# FPGA_Bank_1.net
KiCad netlist of a schematic drawn in Altium Designer
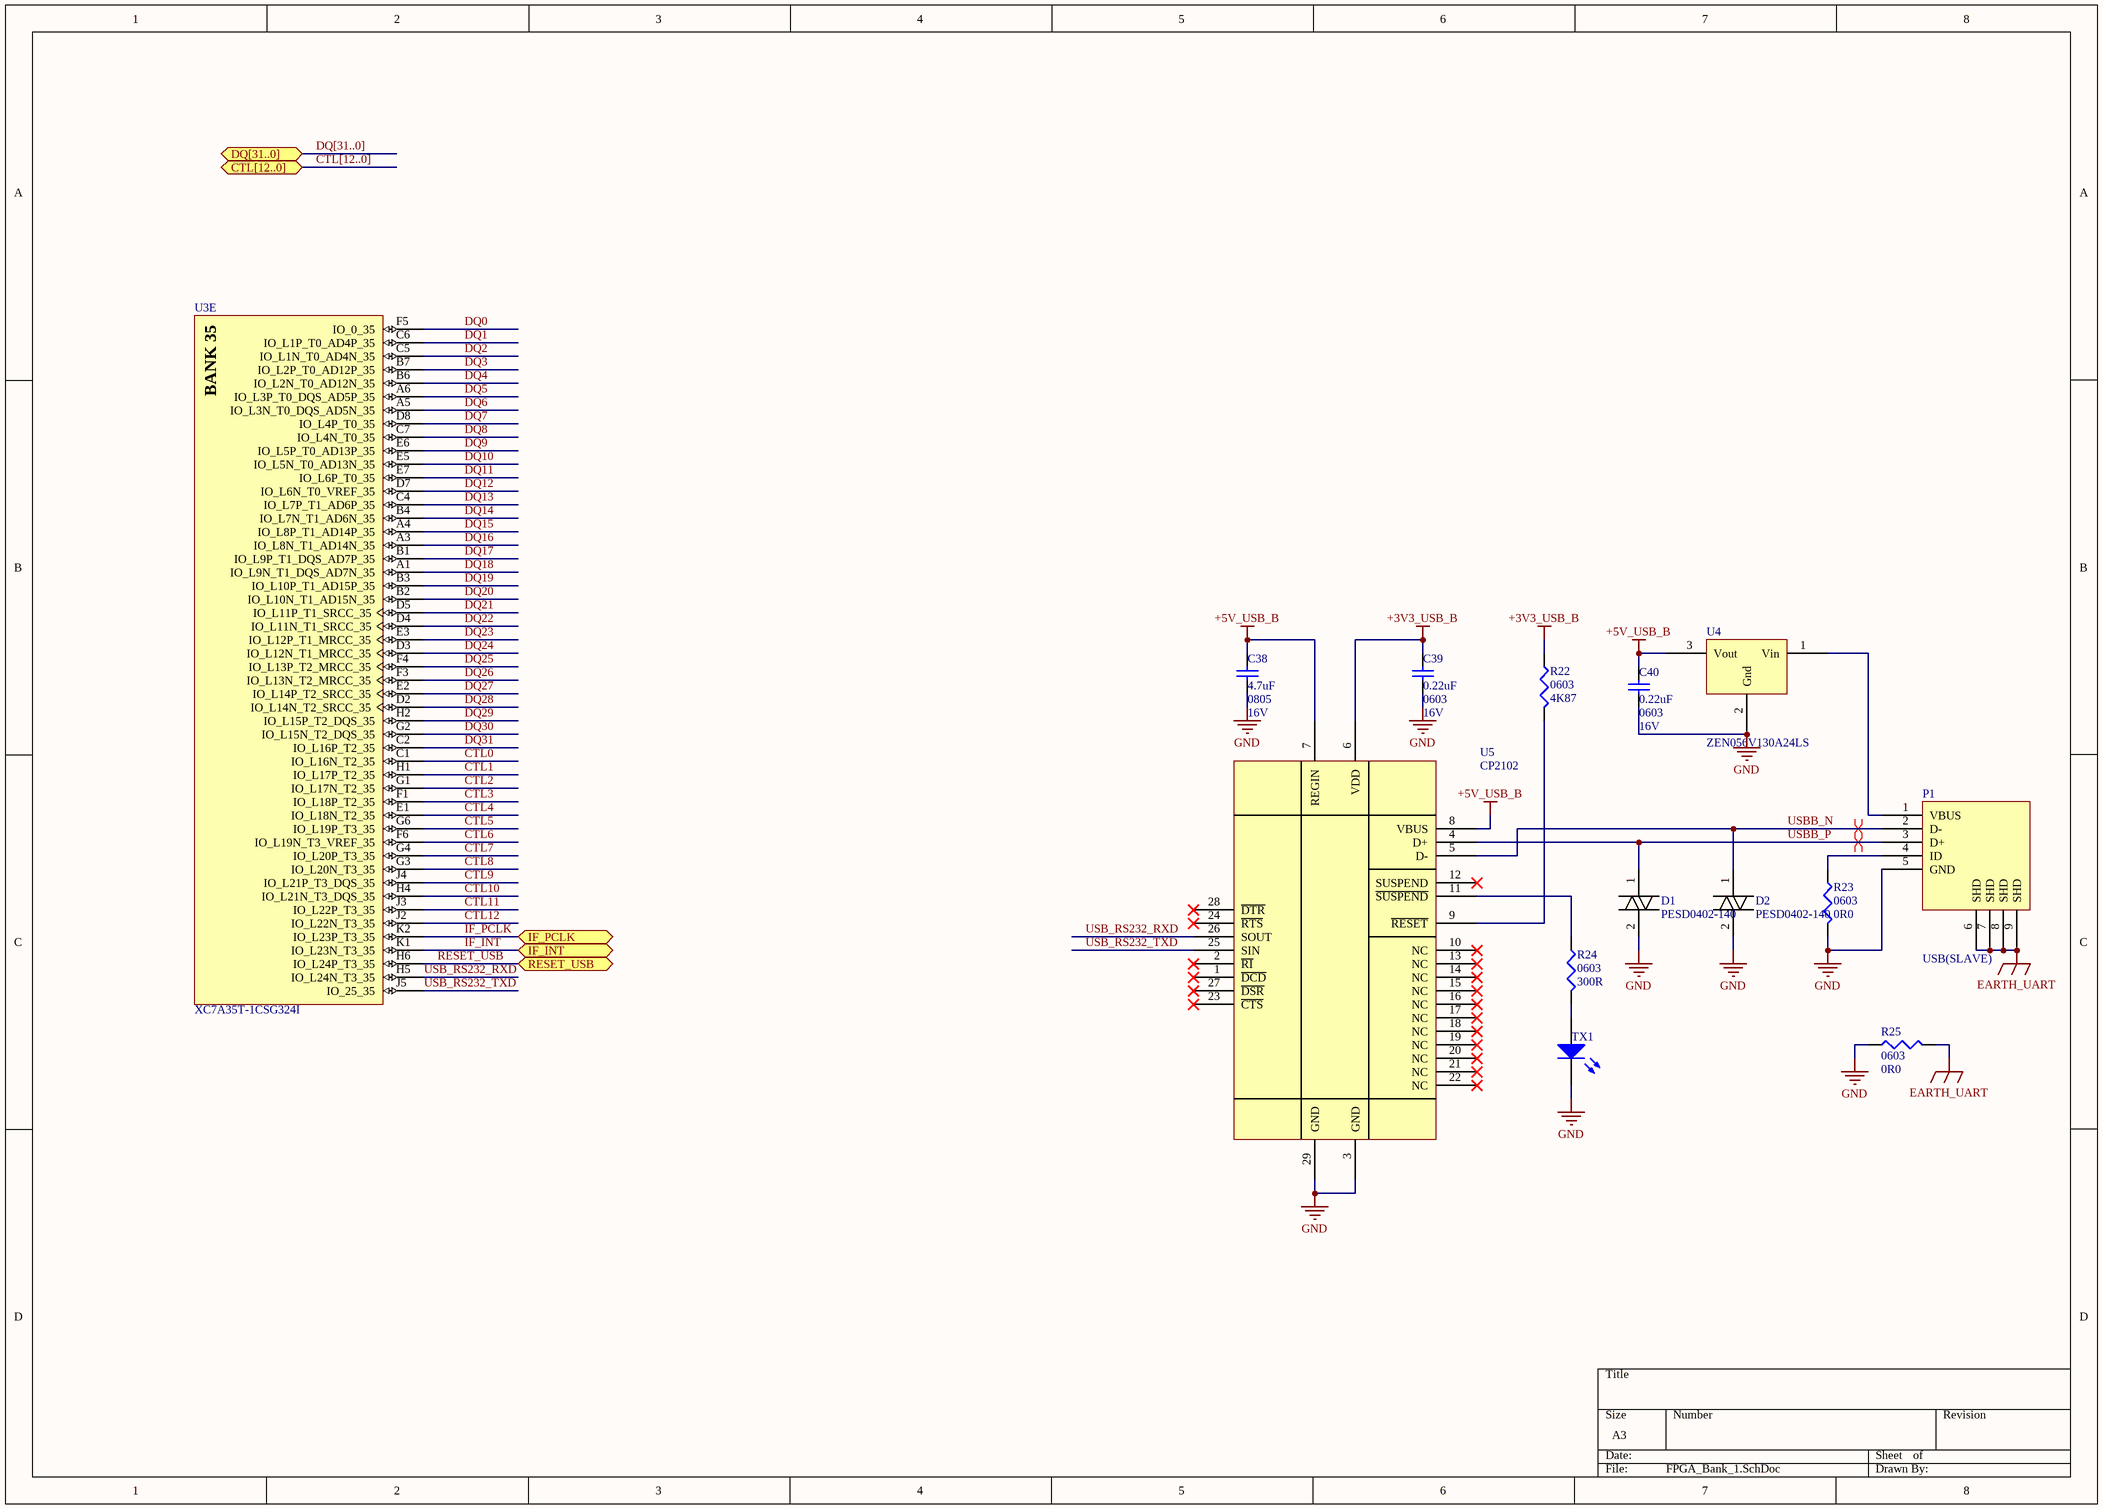
[diagram p0: FPGA_Bank_1.SchDoc]

(export (version "E")
  (design (tool "Eeschema 10.0.6"))
  (components
    (comp (ref "C38")
      (value "4.7uF")
      (footprint "2012[0805]")
      (description "Capacitor (Semiconductor SIM Model)")
      (fields
        (field (name "PACKAGEREFERENCE") "0805")
        (field (name "V") "16V")
        (field (name "PUBLISHER") "Altium Limited")
      )
      (libsource (lib "Devices") (part "Cap Semi"))
    )
    (comp (ref "C39")
      (value "0.22uF")
      (footprint "1608[0603]")
      (description "Capacitor (Semiconductor SIM Model)")
      (fields
        (field (name "PACKAGEREFERENCE") "0603")
        (field (name "V") "16V")
        (field (name "PUBLISHER") "Altium Limited")
      )
      (libsource (lib "Devices") (part "Cap Semi"))
    )
    (comp (ref "C40")
      (value "0.22uF")
      (footprint "1608[0603]")
      (description "Capacitor (Semiconductor SIM Model)")
      (fields
        (field (name "PACKAGEREFERENCE") "0603")
        (field (name "V") "16V")
        (field (name "PUBLISHER") "Altium Limited")
      )
      (libsource (lib "Devices") (part "Cap Semi"))
    )
    (comp (ref "D1")
      (value "PESD0402-140")
      (footprint "PESD0402-140")
      (description "ESD保护器件")
      (libsource (lib "Spartan6_LX9_A0") (part "PESD0402-140"))
    )
    (comp (ref "D2")
      (value "PESD0402-140")
      (footprint "PESD0402-140")
      (description "ESD保护器件")
      (libsource (lib "Spartan6_LX9_A0") (part "PESD0402-140"))
    )
    (comp (ref "P1")
      (value "USB(SLAVE)")
      (footprint "USB_MINI_Btype")
      (description "USB座")
      (libsource (lib "Spartan6_LX9_A0") (part "USB(SLAVE)"))
    )
    (comp (ref "R22")
      (value "4K87")
      (footprint "1608[0603]")
      (description "Resistor")
      (fields
        (field (name "PACKAGEREFERENCE") "0603")
        (field (name "Comment") "Res3")
        (field (name "PUBLISHER") "Altium Limited")
      )
      (libsource (lib "Miscellaneous Devices") (part "Res3"))
    )
    (comp (ref "R23")
      (value "0R0")
      (footprint "1608[0603]")
      (description "Resistor")
      (fields
        (field (name "PACKAGEREFERENCE") "0603")
        (field (name "Comment") "Res3")
        (field (name "PUBLISHER") "Altium Limited")
      )
      (libsource (lib "Miscellaneous Devices") (part "Res3"))
    )
    (comp (ref "R24")
      (value "300R")
      (footprint "1608[0603]")
      (description "Resistor")
      (fields
        (field (name "PACKAGEREFERENCE") "0603")
        (field (name "Comment") "Res3")
        (field (name "PUBLISHER") "Altium Limited")
      )
      (libsource (lib "Miscellaneous Devices") (part "Res3"))
    )
    (comp (ref "R25")
      (value "0R0")
      (footprint "1608[0603]")
      (description "Resistor")
      (fields
        (field (name "PACKAGEREFERENCE") "0603")
        (field (name "Comment") "Res3")
        (field (name "PUBLISHER") "Altium Limited")
      )
      (libsource (lib "Miscellaneous Devices") (part "Res3"))
    )
    (comp (ref "TX1")
      (value "LINK")
      (footprint "0805LED")
      (description "Typical INFRARED GaAs LED")
      (fields (field (name "PUBLISHER") "Altium Limited"))
      (libsource (lib "Miscellaneous Devices") (part "LED0"))
    )
    (comp (ref "U3")
      (value "XC7A35T-1CSG324I")
      (footprint "CSG324")
      (description "Artix-7 FPGA, 210 User I/Os, 0 GTP, 324-Ball BGA, Speed Grade 1, Industrial Grade, Pb-Free")
      (fields (field (name "MANUFACTURER") "Xilinx"))
      (libsource (lib "Xilinx Artix-7") (part "XC7A35T-1CSG324I"))
    )
    (comp (ref "U4")
      (value "ZEN056V130A24LS")
      (footprint "ZEN056")
      (description "电压瞬态抑制器")
      (libsource (lib "Spartan6_LX9_A0") (part "ZEN056V130A24LS"))
    )
    (comp (ref "U5")
      (value "CP2102")
      (footprint "CP2102[QFN28]")
      (description "Single Chip USB to UART Bridge")
      (fields (field (name "MANF") "Silicon Labs"))
      (libsource (lib "Spartan6_LX9_A0") (part "CP2102"))
    )
  )
  (nets
    (net (code "1") (name "+3V3_USB_B") (class "Default")
      (node (ref "C39") (pin "1") (pinfunction "1_1") (pintype "passive"))
      (node (ref "R22") (pin "1") (pinfunction "1_1") (pintype "passive"))
      (node (ref "U5") (pin "6") (pinfunction "VDD_6") (pintype "passive"))
    )
    (net (code "2") (name "+5V_USB_B") (class "Default")
      (node (ref "C38") (pin "1") (pinfunction "1_1") (pintype "passive"))
      (node (ref "C40") (pin "1") (pinfunction "1_1") (pintype "passive"))
      (node (ref "U4") (pin "3") (pinfunction "Vout_3") (pintype "passive"))
      (node (ref "U5") (pin "7") (pinfunction "REGIN_7") (pintype "passive"))
      (node (ref "U5") (pin "8") (pinfunction "VBUS_8") (pintype "passive"))
    )
    (net (code "3") (name "/CTL0") (class "Default")
      (node (ref "U3") (pin "C1") (pinfunction "IO_L16N_T2_35_C1") (pintype "bidirectional"))
    )
    (net (code "4") (name "/CTL1") (class "Default")
      (node (ref "U3") (pin "H1") (pinfunction "IO_L17P_T2_35_H1") (pintype "bidirectional"))
    )
    (net (code "5") (name "/CTL2") (class "Default")
      (node (ref "U3") (pin "G1") (pinfunction "IO_L17N_T2_35_G1") (pintype "bidirectional"))
    )
    (net (code "6") (name "/CTL3") (class "Default")
      (node (ref "U3") (pin "F1") (pinfunction "IO_L18P_T2_35_F1") (pintype "bidirectional"))
    )
    (net (code "7") (name "/CTL4") (class "Default")
      (node (ref "U3") (pin "E1") (pinfunction "IO_L18N_T2_35_E1") (pintype "bidirectional"))
    )
    (net (code "8") (name "/CTL5") (class "Default")
      (node (ref "U3") (pin "G6") (pinfunction "IO_L19P_T3_35_G6") (pintype "bidirectional"))
    )
    (net (code "9") (name "/CTL6") (class "Default")
      (node (ref "U3") (pin "F6") (pinfunction "IO_L19N_T3_VREF_35_F6") (pintype "bidirectional"))
    )
    (net (code "10") (name "/CTL7") (class "Default")
      (node (ref "U3") (pin "G4") (pinfunction "IO_L20P_T3_35_G4") (pintype "bidirectional"))
    )
    (net (code "11") (name "/CTL8") (class "Default")
      (node (ref "U3") (pin "G3") (pinfunction "IO_L20N_T3_35_G3") (pintype "bidirectional"))
    )
    (net (code "12") (name "/CTL9") (class "Default")
      (node (ref "U3") (pin "J4") (pinfunction "IO_L21P_T3_DQS_35_J4") (pintype "bidirectional"))
    )
    (net (code "13") (name "/CTL10") (class "Default")
      (node (ref "U3") (pin "H4") (pinfunction "IO_L21N_T3_DQS_35_H4") (pintype "bidirectional"))
    )
    (net (code "14") (name "/CTL11") (class "Default")
      (node (ref "U3") (pin "J3") (pinfunction "IO_L22P_T3_35_J3") (pintype "bidirectional"))
    )
    (net (code "15") (name "/CTL12") (class "Default")
      (node (ref "U3") (pin "J2") (pinfunction "IO_L22N_T3_35_J2") (pintype "bidirectional"))
    )
    (net (code "17") (name "/DQ0") (class "Default")
      (node (ref "U3") (pin "F5") (pinfunction "IO_0_35_F5") (pintype "bidirectional"))
    )
    (net (code "18") (name "/DQ1") (class "Default")
      (node (ref "U3") (pin "C6") (pinfunction "IO_L1P_T0_AD4P_35_C6") (pintype "bidirectional"))
    )
    (net (code "19") (name "/DQ2") (class "Default")
      (node (ref "U3") (pin "C5") (pinfunction "IO_L1N_T0_AD4N_35_C5") (pintype "bidirectional"))
    )
    (net (code "20") (name "/DQ3") (class "Default")
      (node (ref "U3") (pin "B7") (pinfunction "IO_L2P_T0_AD12P_35_B7") (pintype "bidirectional"))
    )
    (net (code "21") (name "/DQ4") (class "Default")
      (node (ref "U3") (pin "B6") (pinfunction "IO_L2N_T0_AD12N_35_B6") (pintype "bidirectional"))
    )
    (net (code "22") (name "/DQ5") (class "Default")
      (node (ref "U3") (pin "A6") (pinfunction "IO_L3P_T0_DQS_AD5P_35_A6") (pintype "bidirectional"))
    )
    (net (code "23") (name "/DQ6") (class "Default")
      (node (ref "U3") (pin "A5") (pinfunction "IO_L3N_T0_DQS_AD5N_35_A5") (pintype "bidirectional"))
    )
    (net (code "24") (name "/DQ7") (class "Default")
      (node (ref "U3") (pin "D8") (pinfunction "IO_L4P_T0_35_D8") (pintype "bidirectional"))
    )
    (net (code "25") (name "/DQ8") (class "Default")
      (node (ref "U3") (pin "C7") (pinfunction "IO_L4N_T0_35_C7") (pintype "bidirectional"))
    )
    (net (code "26") (name "/DQ9") (class "Default")
      (node (ref "U3") (pin "E6") (pinfunction "IO_L5P_T0_AD13P_35_E6") (pintype "bidirectional"))
    )
    (net (code "27") (name "/DQ10") (class "Default")
      (node (ref "U3") (pin "E5") (pinfunction "IO_L5N_T0_AD13N_35_E5") (pintype "bidirectional"))
    )
    (net (code "28") (name "/DQ11") (class "Default")
      (node (ref "U3") (pin "E7") (pinfunction "IO_L6P_T0_35_E7") (pintype "bidirectional"))
    )
    (net (code "29") (name "/DQ12") (class "Default")
      (node (ref "U3") (pin "D7") (pinfunction "IO_L6N_T0_VREF_35_D7") (pintype "bidirectional"))
    )
    (net (code "30") (name "/DQ13") (class "Default")
      (node (ref "U3") (pin "C4") (pinfunction "IO_L7P_T1_AD6P_35_C4") (pintype "bidirectional"))
    )
    (net (code "31") (name "/DQ14") (class "Default")
      (node (ref "U3") (pin "B4") (pinfunction "IO_L7N_T1_AD6N_35_B4") (pintype "bidirectional"))
    )
    (net (code "32") (name "/DQ15") (class "Default")
      (node (ref "U3") (pin "A4") (pinfunction "IO_L8P_T1_AD14P_35_A4") (pintype "bidirectional"))
    )
    (net (code "33") (name "/DQ16") (class "Default")
      (node (ref "U3") (pin "A3") (pinfunction "IO_L8N_T1_AD14N_35_A3") (pintype "bidirectional"))
    )
    (net (code "34") (name "/DQ17") (class "Default")
      (node (ref "U3") (pin "B1") (pinfunction "IO_L9P_T1_DQS_AD7P_35_B1") (pintype "bidirectional"))
    )
    (net (code "35") (name "/DQ18") (class "Default")
      (node (ref "U3") (pin "A1") (pinfunction "IO_L9N_T1_DQS_AD7N_35_A1") (pintype "bidirectional"))
    )
    (net (code "36") (name "/DQ19") (class "Default")
      (node (ref "U3") (pin "B3") (pinfunction "IO_L10P_T1_AD15P_35_B3") (pintype "bidirectional"))
    )
    (net (code "37") (name "/DQ20") (class "Default")
      (node (ref "U3") (pin "B2") (pinfunction "IO_L10N_T1_AD15N_35_B2") (pintype "bidirectional"))
    )
    (net (code "38") (name "/DQ21") (class "Default")
      (node (ref "U3") (pin "D5") (pinfunction "IO_L11P_T1_SRCC_35_D5") (pintype "bidirectional"))
    )
    (net (code "39") (name "/DQ22") (class "Default")
      (node (ref "U3") (pin "D4") (pinfunction "IO_L11N_T1_SRCC_35_D4") (pintype "bidirectional"))
    )
    (net (code "40") (name "/DQ23") (class "Default")
      (node (ref "U3") (pin "E3") (pinfunction "IO_L12P_T1_MRCC_35_E3") (pintype "bidirectional"))
    )
    (net (code "41") (name "/DQ24") (class "Default")
      (node (ref "U3") (pin "D3") (pinfunction "IO_L12N_T1_MRCC_35_D3") (pintype "bidirectional"))
    )
    (net (code "42") (name "/DQ25") (class "Default")
      (node (ref "U3") (pin "F4") (pinfunction "IO_L13P_T2_MRCC_35_F4") (pintype "bidirectional"))
    )
    (net (code "43") (name "/DQ26") (class "Default")
      (node (ref "U3") (pin "F3") (pinfunction "IO_L13N_T2_MRCC_35_F3") (pintype "bidirectional"))
    )
    (net (code "44") (name "/DQ27") (class "Default")
      (node (ref "U3") (pin "E2") (pinfunction "IO_L14P_T2_SRCC_35_E2") (pintype "bidirectional"))
    )
    (net (code "45") (name "/DQ28") (class "Default")
      (node (ref "U3") (pin "D2") (pinfunction "IO_L14N_T2_SRCC_35_D2") (pintype "bidirectional"))
    )
    (net (code "46") (name "/DQ29") (class "Default")
      (node (ref "U3") (pin "H2") (pinfunction "IO_L15P_T2_DQS_35_H2") (pintype "bidirectional"))
    )
    (net (code "47") (name "/DQ30") (class "Default")
      (node (ref "U3") (pin "G2") (pinfunction "IO_L15N_T2_DQS_35_G2") (pintype "bidirectional"))
    )
    (net (code "48") (name "/DQ31") (class "Default")
      (node (ref "U3") (pin "C2") (pinfunction "IO_L16P_T2_35_C2") (pintype "bidirectional"))
    )
    (net (code "50") (name "/IF_INT") (class "Default")
      (node (ref "U3") (pin "K1") (pinfunction "IO_L23N_T3_35_K1") (pintype "bidirectional"))
    )
    (net (code "51") (name "/IF_PCLK") (class "Default")
      (node (ref "U3") (pin "K2") (pinfunction "IO_L23P_T3_35_K2") (pintype "bidirectional"))
    )
    (net (code "52") (name "/RESET_USB") (class "Default")
      (node (ref "U3") (pin "H6") (pinfunction "IO_L24P_T3_35_H6") (pintype "bidirectional"))
    )
    (net (code "53") (name "/USBB_N") (class "Default")
      (node (ref "D2") (pin "1") (pinfunction "1_1") (pintype "passive"))
      (node (ref "P1") (pin "2") (pinfunction "D-_2") (pintype "passive"))
      (node (ref "U5") (pin "5") (pinfunction "D-_5") (pintype "passive"))
    )
    (net (code "54") (name "/USBB_P") (class "Default")
      (node (ref "D1") (pin "1") (pinfunction "1_1") (pintype "passive"))
      (node (ref "P1") (pin "3") (pinfunction "D+_3") (pintype "passive"))
      (node (ref "U5") (pin "4") (pinfunction "D+_4") (pintype "passive"))
    )
    (net (code "55") (name "/USB_RS232_RXD") (class "Default")
      (node (ref "U3") (pin "H5") (pinfunction "IO_L24N_T3_35_H5") (pintype "bidirectional"))
      (node (ref "U5") (pin "26") (pinfunction "SOUT_26") (pintype "passive"))
    )
    (net (code "56") (name "/USB_RS232_TXD") (class "Default")
      (node (ref "U3") (pin "J5") (pinfunction "IO_25_35_J5") (pintype "bidirectional"))
      (node (ref "U5") (pin "25") (pinfunction "SIN_25") (pintype "passive"))
    )
    (net (code "57") (name "EARTH_UART") (class "Default")
      (node (ref "P1") (pin "6") (pinfunction "SHD_6") (pintype "passive"))
      (node (ref "P1") (pin "7") (pinfunction "SHD_7") (pintype "passive"))
      (node (ref "P1") (pin "8") (pinfunction "SHD_8") (pintype "passive"))
      (node (ref "P1") (pin "9") (pinfunction "SHD_9") (pintype "passive"))
      (node (ref "R25") (pin "2") (pinfunction "2_2") (pintype "passive"))
    )
    (net (code "58") (name "GND") (class "Default")
      (node (ref "C38") (pin "2") (pinfunction "2_2") (pintype "passive"))
      (node (ref "C39") (pin "2") (pinfunction "2_2") (pintype "passive"))
      (node (ref "C40") (pin "2") (pinfunction "2_2") (pintype "passive"))
      (node (ref "D1") (pin "2") (pinfunction "2_2") (pintype "passive"))
      (node (ref "D2") (pin "2") (pinfunction "2_2") (pintype "passive"))
      (node (ref "P1") (pin "5") (pinfunction "GND_5") (pintype "passive"))
      (node (ref "R23") (pin "2") (pinfunction "2_2") (pintype "passive"))
      (node (ref "R25") (pin "1") (pinfunction "1_1") (pintype "passive"))
      (node (ref "TX1") (pin "2") (pinfunction "K_2") (pintype "passive"))
      (node (ref "U4") (pin "2") (pinfunction "Gnd_2") (pintype "passive"))
      (node (ref "U5") (pin "29") (pinfunction "GND_29") (pintype "passive"))
      (node (ref "U5") (pin "3") (pinfunction "GND_3") (pintype "passive"))
    )
    (net (code "59") (name "Net-(P1-ID)") (class "Default")
      (node (ref "P1") (pin "4") (pinfunction "ID_4") (pintype "passive"))
      (node (ref "R23") (pin "1") (pinfunction "1_1") (pintype "passive"))
    )
    (net (code "60") (name "Net-(P1-VBUS)") (class "Default")
      (node (ref "P1") (pin "1") (pinfunction "VBUS_1") (pintype "passive"))
      (node (ref "U4") (pin "1") (pinfunction "Vin_1") (pintype "passive"))
    )
    (net (code "61") (name "Net-(TX1-A)") (class "Default")
      (node (ref "R24") (pin "2") (pinfunction "2_2") (pintype "passive"))
      (node (ref "TX1") (pin "1") (pinfunction "A_1") (pintype "passive"))
    )
    (net (code "62") (name "Net-(U5-~{RESET})") (class "Default")
      (node (ref "R22") (pin "2") (pinfunction "2_2") (pintype "passive"))
      (node (ref "U5") (pin "9") (pinfunction "~{RESET}_9") (pintype "passive"))
    )
    (net (code "63") (name "Net-(U5-~{SUSPEND})") (class "Default")
      (node (ref "R24") (pin "1") (pinfunction "1_1") (pintype "passive"))
      (node (ref "U5") (pin "11") (pinfunction "~{SUSPEND}_11") (pintype "passive"))
    )
    (net (code "64") (name "unconnected-(U5-NC-Pad10)") (class "Default")
      (node (ref "U5") (pin "10") (pinfunction "NC_10") (pintype "passive+no_connect"))
    )
    (net (code "65") (name "unconnected-(U5-NC-Pad13)") (class "Default")
      (node (ref "U5") (pin "13") (pinfunction "NC_13") (pintype "passive+no_connect"))
    )
    (net (code "66") (name "unconnected-(U5-NC-Pad14)") (class "Default")
      (node (ref "U5") (pin "14") (pinfunction "NC_14") (pintype "passive+no_connect"))
    )
    (net (code "67") (name "unconnected-(U5-NC-Pad15)") (class "Default")
      (node (ref "U5") (pin "15") (pinfunction "NC_15") (pintype "passive+no_connect"))
    )
    (net (code "68") (name "unconnected-(U5-NC-Pad16)") (class "Default")
      (node (ref "U5") (pin "16") (pinfunction "NC_16") (pintype "passive+no_connect"))
    )
    (net (code "69") (name "unconnected-(U5-NC-Pad17)") (class "Default")
      (node (ref "U5") (pin "17") (pinfunction "NC_17") (pintype "passive+no_connect"))
    )
    (net (code "70") (name "unconnected-(U5-NC-Pad18)") (class "Default")
      (node (ref "U5") (pin "18") (pinfunction "NC_18") (pintype "passive+no_connect"))
    )
    (net (code "71") (name "unconnected-(U5-NC-Pad19)") (class "Default")
      (node (ref "U5") (pin "19") (pinfunction "NC_19") (pintype "passive+no_connect"))
    )
    (net (code "72") (name "unconnected-(U5-NC-Pad20)") (class "Default")
      (node (ref "U5") (pin "20") (pinfunction "NC_20") (pintype "passive+no_connect"))
    )
    (net (code "73") (name "unconnected-(U5-NC-Pad21)") (class "Default")
      (node (ref "U5") (pin "21") (pinfunction "NC_21") (pintype "passive+no_connect"))
    )
    (net (code "74") (name "unconnected-(U5-NC-Pad22)") (class "Default")
      (node (ref "U5") (pin "22") (pinfunction "NC_22") (pintype "passive+no_connect"))
    )
    (net (code "75") (name "unconnected-(U5-SUSPEND-Pad12)") (class "Default")
      (node (ref "U5") (pin "12") (pinfunction "SUSPEND_12") (pintype "passive+no_connect"))
    )
    (net (code "76") (name "unconnected-(U5-~{CTS}-Pad23)") (class "Default")
      (node (ref "U5") (pin "23") (pinfunction "~{CTS}_23") (pintype "passive+no_connect"))
    )
    (net (code "77") (name "unconnected-(U5-~{DCD}-Pad1)") (class "Default")
      (node (ref "U5") (pin "1") (pinfunction "~{DCD}_1") (pintype "passive+no_connect"))
    )
    (net (code "78") (name "unconnected-(U5-~{DSR}-Pad27)") (class "Default")
      (node (ref "U5") (pin "27") (pinfunction "~{DSR}_27") (pintype "passive+no_connect"))
    )
    (net (code "79") (name "unconnected-(U5-~{DTR}-Pad28)") (class "Default")
      (node (ref "U5") (pin "28") (pinfunction "~{DTR}_28") (pintype "passive+no_connect"))
    )
    (net (code "80") (name "unconnected-(U5-~{RI}-Pad2)") (class "Default")
      (node (ref "U5") (pin "2") (pinfunction "~{RI}_2") (pintype "passive+no_connect"))
    )
    (net (code "81") (name "unconnected-(U5-~{RTS}-Pad24)") (class "Default")
      (node (ref "U5") (pin "24") (pinfunction "~{RTS}_24") (pintype "passive+no_connect"))
    )
  )
)
